# amp_pcb.net
KiCad netlist of a schematic drawn in EAGLE
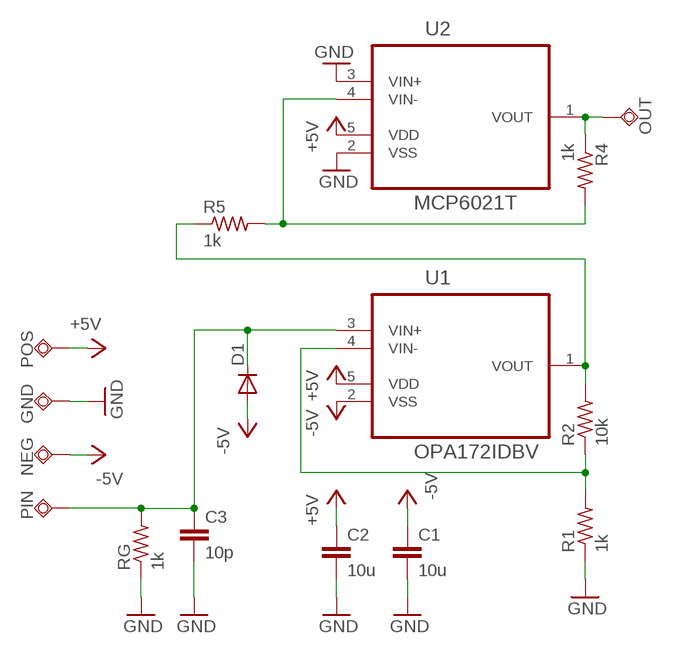
[diagram p0: schematic, sheet 1]

(export (version "E")
  (design (tool "Eeschema 10.0.6"))
  (components
    (comp (ref "C1")
      (value "10u")
      (footprint "eagle-import:C0603")
      (libsource (lib "eagle-import") (part "C-EUC0603"))
    )
    (comp (ref "C2")
      (value "10u")
      (footprint "eagle-import:C0603")
      (libsource (lib "eagle-import") (part "C-EUC0603"))
    )
    (comp (ref "C3")
      (value "10p")
      (footprint "eagle-import:C0603")
      (libsource (lib "eagle-import") (part "C-EUC0603"))
    )
    (comp (ref "D1")
      (value "DIODE-DO214AA")
      (footprint "eagle-import:DO214AA")
      (libsource (lib "eagle-import") (part "DIODE-DO214AA"))
    )
    (comp (ref "GND")
      (value "TPSQTP15SQ")
      (footprint "eagle-import:TP15SQ")
      (libsource (lib "eagle-import") (part "TPSQTP15SQ"))
    )
    (comp (ref "NEG")
      (value "TPSQTP15SQ")
      (footprint "eagle-import:TP15SQ")
      (libsource (lib "eagle-import") (part "TPSQTP15SQ"))
    )
    (comp (ref "OUT")
      (value "TPSQTP15SQ")
      (footprint "eagle-import:TP15SQ")
      (libsource (lib "eagle-import") (part "TPSQTP15SQ"))
    )
    (comp (ref "PIN")
      (value "TPSQTP15SQ")
      (footprint "eagle-import:TP15SQ")
      (libsource (lib "eagle-import") (part "TPSQTP15SQ"))
    )
    (comp (ref "POS")
      (value "TPSQTP15SQ")
      (footprint "eagle-import:TP15SQ")
      (libsource (lib "eagle-import") (part "TPSQTP15SQ"))
    )
    (comp (ref "R1")
      (value "1k")
      (footprint "eagle-import:R0603")
      (libsource (lib "eagle-import") (part "R-US_R0603"))
    )
    (comp (ref "R2")
      (value "10k")
      (footprint "eagle-import:R0603")
      (libsource (lib "eagle-import") (part "R-US_R0603"))
    )
    (comp (ref "R4")
      (value "1k")
      (footprint "eagle-import:R0603")
      (libsource (lib "eagle-import") (part "R-US_R0603"))
    )
    (comp (ref "R5")
      (value "1k")
      (footprint "eagle-import:R0603")
      (libsource (lib "eagle-import") (part "R-US_R0603"))
    )
    (comp (ref "RG")
      (value "1k")
      (footprint "eagle-import:R0603")
      (libsource (lib "eagle-import") (part "R-US_R0603"))
    )
    (comp (ref "U1")
      (value "OPA172IDBV")
      (footprint "eagle-import:SOT95P320X145-5N")
      (fields (field (name "MPN") "MCP6021T-E/OT"))
      (libsource (lib "eagle-import") (part "MCP6021T-E/OT"))
    )
    (comp (ref "U2")
      (value "MCP6021T")
      (footprint "eagle-import:SOT95P320X145-5N")
      (fields (field (name "MPN") "MCP6021T-E/OT"))
      (libsource (lib "eagle-import") (part "MCP6021T-E/OT"))
    )
  )
  (nets
    (net (code "1") (name "+5V") (class "Default")
      (node (ref "C2") (pin "1") (pinfunction "1_1") (pintype "passive"))
      (node (ref "POS") (pin "TP") (pinfunction "TP_TP") (pintype "input"))
      (node (ref "U1") (pin "5") (pinfunction "VDD_5") (pintype "power_in"))
      (node (ref "U2") (pin "5") (pinfunction "VDD_5") (pintype "power_in"))
    )
    (net (code "2") (name "-5V") (class "Default")
      (node (ref "C1") (pin "1") (pinfunction "1_1") (pintype "passive"))
      (node (ref "D1") (pin "A") (pinfunction "A_A") (pintype "passive"))
      (node (ref "NEG") (pin "TP") (pinfunction "TP_TP") (pintype "input"))
      (node (ref "U1") (pin "2") (pinfunction "VSS_2") (pintype "passive"))
    )
    (net (code "3") (name "GND") (class "Default")
      (node (ref "C1") (pin "2") (pinfunction "2_2") (pintype "passive"))
      (node (ref "C2") (pin "2") (pinfunction "2_2") (pintype "passive"))
      (node (ref "C3") (pin "2") (pinfunction "2_2") (pintype "passive"))
      (node (ref "GND") (pin "TP") (pinfunction "TP_TP") (pintype "input"))
      (node (ref "R1") (pin "1") (pinfunction "1_1") (pintype "passive"))
      (node (ref "RG") (pin "1") (pinfunction "1_1") (pintype "passive"))
      (node (ref "U2") (pin "2") (pinfunction "VSS_2") (pintype "passive"))
      (node (ref "U2") (pin "3") (pinfunction "VIN+_3") (pintype "input"))
    )
    (net (code "4") (name "Net-(U1-VIN+)") (class "Default")
      (node (ref "C3") (pin "1") (pinfunction "1_1") (pintype "passive"))
      (node (ref "D1") (pin "C") (pinfunction "C_C") (pintype "passive"))
      (node (ref "PIN") (pin "TP") (pinfunction "TP_TP") (pintype "input"))
      (node (ref "RG") (pin "2") (pinfunction "2_2") (pintype "passive"))
      (node (ref "U1") (pin "3") (pinfunction "VIN+_3") (pintype "input"))
    )
    (net (code "5") (name "Net-(U1-VIN-)") (class "Default")
      (node (ref "R1") (pin "2") (pinfunction "2_2") (pintype "passive"))
      (node (ref "R2") (pin "1") (pinfunction "1_1") (pintype "passive"))
      (node (ref "U1") (pin "4") (pinfunction "VIN-_4") (pintype "input"))
    )
    (net (code "6") (name "Net-(U1-VOUT)") (class "Default")
      (node (ref "R2") (pin "2") (pinfunction "2_2") (pintype "passive"))
      (node (ref "R5") (pin "1") (pinfunction "1_1") (pintype "passive"))
      (node (ref "U1") (pin "1") (pinfunction "VOUT_1") (pintype "output"))
    )
    (net (code "7") (name "Net-(U2-VIN-)") (class "Default")
      (node (ref "R4") (pin "2") (pinfunction "2_2") (pintype "passive"))
      (node (ref "R5") (pin "2") (pinfunction "2_2") (pintype "passive"))
      (node (ref "U2") (pin "4") (pinfunction "VIN-_4") (pintype "input"))
    )
    (net (code "8") (name "Net-(U2-VOUT)") (class "Default")
      (node (ref "OUT") (pin "TP") (pinfunction "TP_TP") (pintype "input"))
      (node (ref "R4") (pin "1") (pinfunction "1_1") (pintype "passive"))
      (node (ref "U2") (pin "1") (pinfunction "VOUT_1") (pintype "output"))
    )
  )
)
